# SUMO_ROBOT.net
KiCad netlist of a schematic drawn in EAGLE
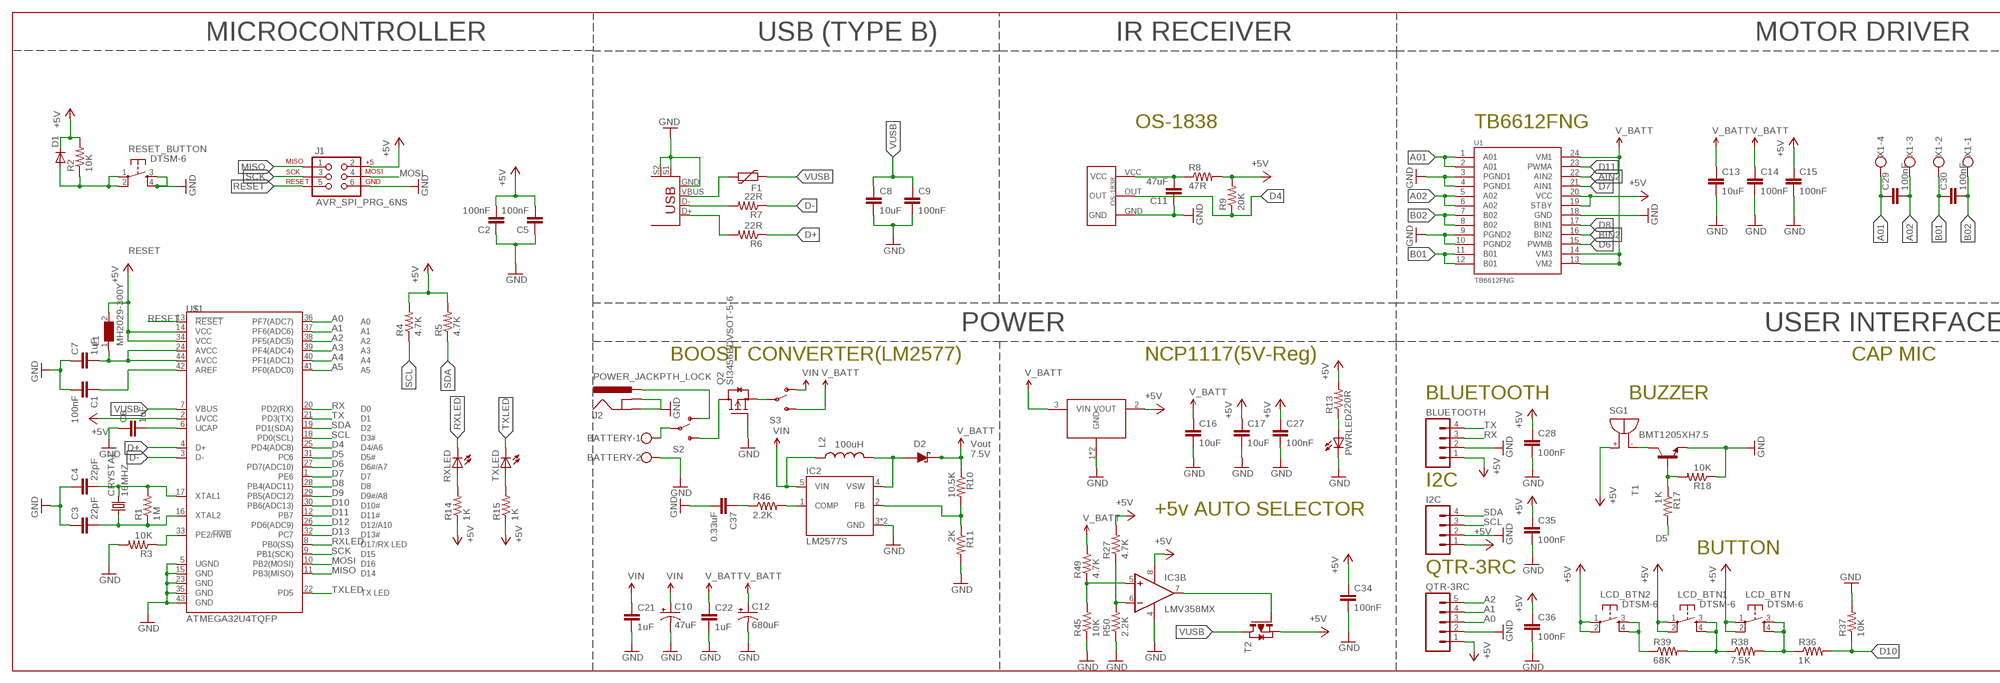
[diagram p0: schematic, sheet 1, part 1 of 2]
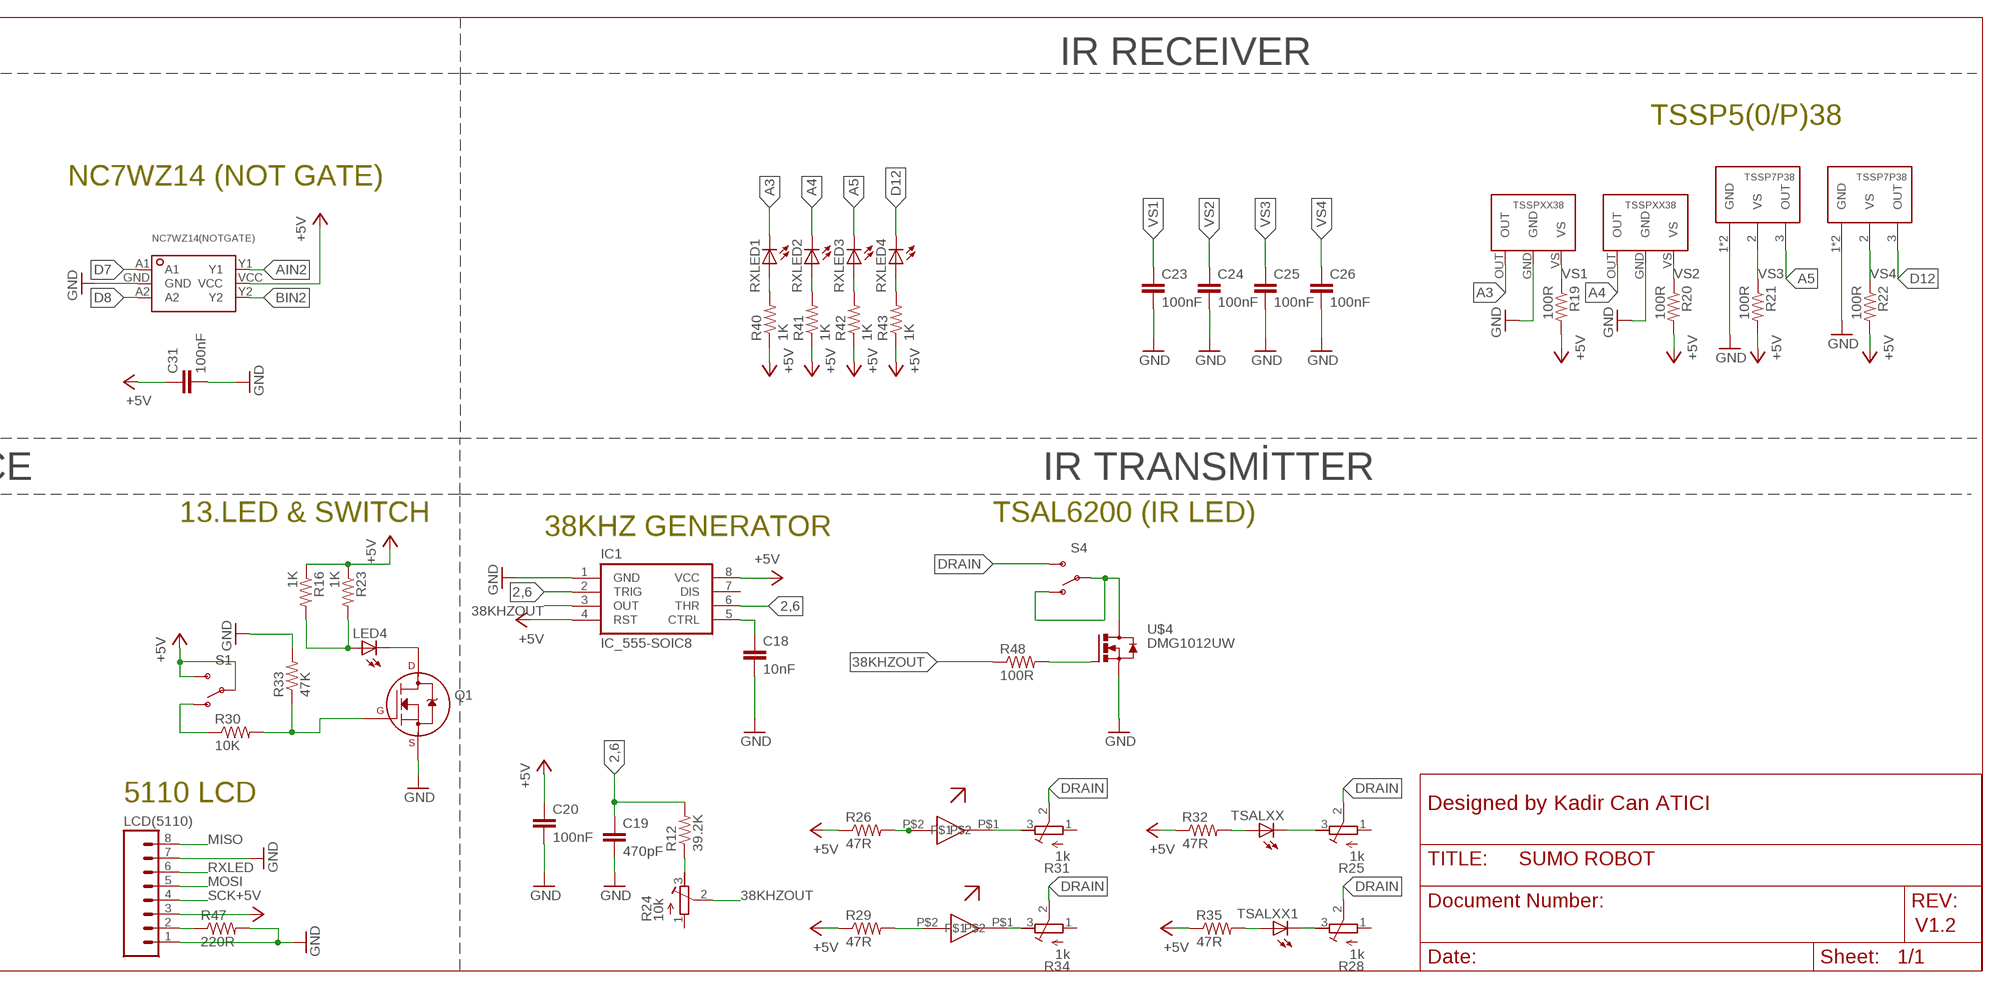
[diagram p1: schematic, sheet 1, part 2 of 2]

(export (version "E")
  (design (tool "Eeschema 10.0.6"))
  (components
    (comp (ref "BATTERY")
      (value "W237-102")
      (footprint "eagle-import:W237-102")
      (fields (field (name "MPN") "237-102"))
      (libsource (lib "eagle-import") (part "W237-102"))
    )
    (comp (ref "BLUETOOTH")
      (value "M04PTH")
      (footprint "eagle-import:1X04")
      (libsource (lib "eagle-import") (part "M04PTH"))
    )
    (comp (ref "C1")
      (value "100nF")
      (footprint "eagle-import:1206")
      (libsource (lib "eagle-import") (part "CAP1206"))
    )
    (comp (ref "C2")
      (value "100nF")
      (footprint "eagle-import:1206")
      (libsource (lib "eagle-import") (part "CAP1206"))
    )
    (comp (ref "C3")
      (value "22pF")
      (footprint "eagle-import:1206")
      (libsource (lib "eagle-import") (part "CAP1206"))
    )
    (comp (ref "C4")
      (value "22pF")
      (footprint "eagle-import:1206")
      (libsource (lib "eagle-import") (part "CAP1206"))
    )
    (comp (ref "C5")
      (value "100nF")
      (footprint "eagle-import:1206")
      (libsource (lib "eagle-import") (part "CAP1206"))
    )
    (comp (ref "C6")
      (value "1uF")
      (footprint "eagle-import:1206")
      (libsource (lib "eagle-import") (part "CAP1206"))
    )
    (comp (ref "C7")
      (value "1uF")
      (footprint "eagle-import:1206")
      (libsource (lib "eagle-import") (part "CAP1206"))
    )
    (comp (ref "C8")
      (value "10uF")
      (footprint "eagle-import:1206")
      (libsource (lib "eagle-import") (part "CAP1206"))
    )
    (comp (ref "C9")
      (value "100nF")
      (footprint "eagle-import:1206")
      (libsource (lib "eagle-import") (part "CAP1206"))
    )
    (comp (ref "C10")
      (value "47uF")
      (footprint "eagle-import:NIPPON_F80")
      (libsource (lib "eagle-import") (part "CAP_POLF80"))
    )
    (comp (ref "C11")
      (value "47uF")
      (footprint "eagle-import:1206")
      (libsource (lib "eagle-import") (part "CAP1206"))
    )
    (comp (ref "C12")
      (value "680uF")
      (footprint "eagle-import:PANASONIC_G")
      (libsource (lib "eagle-import") (part "CAP_POLG"))
    )
    (comp (ref "C13")
      (value "10uF")
      (footprint "eagle-import:1206")
      (libsource (lib "eagle-import") (part "CAP1206"))
    )
    (comp (ref "C14")
      (value "100nF")
      (footprint "eagle-import:1206")
      (libsource (lib "eagle-import") (part "CAP1206"))
    )
    (comp (ref "C15")
      (value "100nF")
      (footprint "eagle-import:1206")
      (libsource (lib "eagle-import") (part "CAP1206"))
    )
    (comp (ref "C16")
      (value "10uF")
      (footprint "eagle-import:1206")
      (libsource (lib "eagle-import") (part "CAP1206"))
    )
    (comp (ref "C17")
      (value "10uF")
      (footprint "eagle-import:1206")
      (libsource (lib "eagle-import") (part "CAP1206"))
    )
    (comp (ref "C18")
      (value "10nF")
      (footprint "eagle-import:1206")
      (libsource (lib "eagle-import") (part "CAP1206"))
    )
    (comp (ref "C19")
      (value "470pF")
      (footprint "eagle-import:1206")
      (libsource (lib "eagle-import") (part "CAP1206"))
    )
    (comp (ref "C20")
      (value "100nF")
      (footprint "eagle-import:1206")
      (libsource (lib "eagle-import") (part "CAP1206"))
    )
    (comp (ref "C21")
      (value "1uF")
      (footprint "eagle-import:1206")
      (libsource (lib "eagle-import") (part "CAP1206"))
    )
    (comp (ref "C22")
      (value "1uF")
      (footprint "eagle-import:1206")
      (libsource (lib "eagle-import") (part "CAP1206"))
    )
    (comp (ref "C23")
      (value "100nF")
      (footprint "eagle-import:1206")
      (libsource (lib "eagle-import") (part "CAP1206"))
    )
    (comp (ref "C24")
      (value "100nF")
      (footprint "eagle-import:1206")
      (libsource (lib "eagle-import") (part "CAP1206"))
    )
    (comp (ref "C25")
      (value "100nF")
      (footprint "eagle-import:1206")
      (libsource (lib "eagle-import") (part "CAP1206"))
    )
    (comp (ref "C26")
      (value "100nF")
      (footprint "eagle-import:1206")
      (libsource (lib "eagle-import") (part "CAP1206"))
    )
    (comp (ref "C27")
      (value "100nF")
      (footprint "eagle-import:1206")
      (libsource (lib "eagle-import") (part "CAP1206"))
    )
    (comp (ref "C28")
      (value "100nF")
      (footprint "eagle-import:1206")
      (libsource (lib "eagle-import") (part "CAP1206"))
    )
    (comp (ref "C29")
      (value "100nF")
      (footprint "eagle-import:1206")
      (libsource (lib "eagle-import") (part "CAP1206"))
    )
    (comp (ref "C30")
      (value "100nF")
      (footprint "eagle-import:1206")
      (libsource (lib "eagle-import") (part "CAP1206"))
    )
    (comp (ref "C31")
      (value "100nF")
      (footprint "eagle-import:1206")
      (libsource (lib "eagle-import") (part "CAP1206"))
    )
    (comp (ref "C34")
      (value "100nF")
      (footprint "eagle-import:1206")
      (libsource (lib "eagle-import") (part "CAP1206"))
    )
    (comp (ref "C35")
      (value "100nF")
      (footprint "eagle-import:1206")
      (libsource (lib "eagle-import") (part "CAP1206"))
    )
    (comp (ref "C36")
      (value "100nF")
      (footprint "eagle-import:1206")
      (libsource (lib "eagle-import") (part "CAP1206"))
    )
    (comp (ref "C37")
      (value "0.33uF")
      (footprint "eagle-import:1206")
      (libsource (lib "eagle-import") (part "CAP1206"))
    )
    (comp (ref "CRYSTAL")
      (value "16MHZ")
      (footprint "eagle-import:CRYSTAL-SMD-5X3")
      (libsource (lib "eagle-import") (part "CRYSTAL5X3"))
    )
    (comp (ref "D1")
      (value "DIODE-MINIMELF")
      (footprint "eagle-import:MINIMELF")
      (libsource (lib "eagle-import") (part "DIODE-MINIMELF"))
    )
    (comp (ref "D2")
      (value "D_SCHOTTKYA")
      (footprint "eagle-import:SMA")
      (libsource (lib "eagle-import") (part "D_SCHOTTKYA"))
    )
    (comp (ref "F1")
      (value "FUSE_PTC-0805")
      (footprint "eagle-import:PTC0805")
      (libsource (lib "eagle-import") (part "FUSE_PTC-0805"))
    )
    (comp (ref "I2C")
      (value "M04PTH")
      (footprint "eagle-import:1X04")
      (libsource (lib "eagle-import") (part "M04PTH"))
    )
    (comp (ref "IC1")
      (value "IC_555-SOIC8")
      (footprint "eagle-import:SOIC-8")
      (libsource (lib "eagle-import") (part "IC_555-SOIC8"))
    )
    (comp (ref "IC2")
      (value "LM2577S")
      (footprint "eagle-import:TO263-5")
      (libsource (lib "eagle-import") (part "LM2577S"))
    )
    (comp (ref "IC3")
      (value "LMV358MX")
      (footprint "eagle-import:SO08")
      (libsource (lib "eagle-import") (part "LMV358?MX"))
    )
    (comp (ref "J1")
      (value "AVR_SPI_PRG_6NS")
      (footprint "eagle-import:2X3-NS")
      (libsource (lib "eagle-import") (part "AVR_SPI_PRG_6NS"))
    )
    (comp (ref "J2")
      (value "POWER_JACKPTH_LOCK")
      (footprint "eagle-import:POWER_JACK_PTH_LOCK")
      (libsource (lib "eagle-import") (part "POWER_JACKPTH_LOCK"))
    )
    (comp (ref "L1")
      (value "MH2029-300Y")
      (footprint "eagle-import:0805")
      (libsource (lib "eagle-import") (part "WE-CBF_0805"))
    )
    (comp (ref "L2")
      (value "INDUCTORPWR")
      (footprint "eagle-import:CDRH125")
      (libsource (lib "eagle-import") (part "INDUCTORPWR"))
    )
    (comp (ref "LCD(5110)")
      (value "M081X08")
      (footprint "eagle-import:1X08")
      (libsource (lib "eagle-import") (part "M081X08"))
    )
    (comp (ref "LCD_BTN")
      (value "DTSM-6")
      (footprint "eagle-import:DTSM-6")
      (libsource (lib "eagle-import") (part "DTSM-6"))
    )
    (comp (ref "LCD_BTN1")
      (value "DTSM-6")
      (footprint "eagle-import:DTSM-6")
      (libsource (lib "eagle-import") (part "DTSM-6"))
    )
    (comp (ref "LCD_BTN2")
      (value "DTSM-6")
      (footprint "eagle-import:DTSM-6")
      (libsource (lib "eagle-import") (part "DTSM-6"))
    )
    (comp (ref "LED4")
      (value "LEDCHIPLED_0805")
      (footprint "eagle-import:CHIPLED_0805")
      (libsource (lib "eagle-import") (part "LEDCHIPLED_0805"))
    )
    (comp (ref "PWRLED")
      (value "LEDCHIPLED_0805")
      (footprint "eagle-import:CHIPLED_0805")
      (libsource (lib "eagle-import") (part "LEDCHIPLED_0805"))
    )
    (comp (ref "Q1")
      (value "2N7000_SOT23")
      (footprint "eagle-import:SOT-23")
      (libsource (lib "eagle-import") (part "2N700_SOT230"))
    )
    (comp (ref "Q2")
      (value "SI3456BDVSOT-5-6")
      (footprint "eagle-import:SOT23-6")
      (libsource (lib "eagle-import") (part "SI3456BDVSOT-5-6"))
    )
    (comp (ref "QTR-3RC")
      (value "M05PTH")
      (footprint "eagle-import:1X05")
      (libsource (lib "eagle-import") (part "M05PTH"))
    )
    (comp (ref "R1")
      (value "1M")
      (footprint "eagle-import:0805")
      (libsource (lib "eagle-import") (part "RESISTOR0805-RES"))
    )
    (comp (ref "R2")
      (value "10K")
      (footprint "eagle-import:0805")
      (libsource (lib "eagle-import") (part "RESISTOR0805-RES"))
    )
    (comp (ref "R3")
      (value "10K")
      (footprint "eagle-import:0805")
      (libsource (lib "eagle-import") (part "RESISTOR0805-RES"))
    )
    (comp (ref "R4")
      (value "4.7K")
      (footprint "eagle-import:0805")
      (libsource (lib "eagle-import") (part "RESISTOR0805-RES"))
    )
    (comp (ref "R5")
      (value "4.7K")
      (footprint "eagle-import:0805")
      (libsource (lib "eagle-import") (part "RESISTOR0805-RES"))
    )
    (comp (ref "R6")
      (value "22R")
      (footprint "eagle-import:0805")
      (libsource (lib "eagle-import") (part "RESISTOR0805-RES"))
    )
    (comp (ref "R7")
      (value "22R")
      (footprint "eagle-import:0805")
      (libsource (lib "eagle-import") (part "RESISTOR0805-RES"))
    )
    (comp (ref "R8")
      (value "47R")
      (footprint "eagle-import:0805")
      (libsource (lib "eagle-import") (part "RESISTOR0805-RES"))
    )
    (comp (ref "R9")
      (value "20K")
      (footprint "eagle-import:0805")
      (libsource (lib "eagle-import") (part "RESISTOR0805-RES"))
    )
    (comp (ref "R10")
      (value "10.5K")
      (footprint "eagle-import:0805")
      (libsource (lib "eagle-import") (part "RESISTOR0805-RES"))
    )
    (comp (ref "R11")
      (value "2K")
      (footprint "eagle-import:0805")
      (libsource (lib "eagle-import") (part "RESISTOR0805-RES"))
    )
    (comp (ref "R12")
      (value "39.2K")
      (footprint "eagle-import:0805")
      (libsource (lib "eagle-import") (part "RESISTOR0805-RES"))
    )
    (comp (ref "R13")
      (value "220R")
      (footprint "eagle-import:0805")
      (libsource (lib "eagle-import") (part "RESISTOR0805-RES"))
    )
    (comp (ref "R14")
      (value "1K")
      (footprint "eagle-import:0805")
      (libsource (lib "eagle-import") (part "RESISTOR0805-RES"))
    )
    (comp (ref "R15")
      (value "1K")
      (footprint "eagle-import:0805")
      (libsource (lib "eagle-import") (part "RESISTOR0805-RES"))
    )
    (comp (ref "R16")
      (value "1K")
      (footprint "eagle-import:0805")
      (libsource (lib "eagle-import") (part "RESISTOR0805-RES"))
    )
    (comp (ref "R17")
      (value "1K")
      (footprint "eagle-import:0805")
      (libsource (lib "eagle-import") (part "RESISTOR0805-RES"))
    )
    (comp (ref "R18")
      (value "10K")
      (footprint "eagle-import:0805")
      (libsource (lib "eagle-import") (part "RESISTOR0805-RES"))
    )
    (comp (ref "R19")
      (value "100R")
      (footprint "eagle-import:0805")
      (libsource (lib "eagle-import") (part "RESISTOR0805-RES"))
    )
    (comp (ref "R20")
      (value "100R")
      (footprint "eagle-import:0805")
      (libsource (lib "eagle-import") (part "RESISTOR0805-RES"))
    )
    (comp (ref "R21")
      (value "100R")
      (footprint "eagle-import:0805")
      (libsource (lib "eagle-import") (part "RESISTOR0805-RES"))
    )
    (comp (ref "R22")
      (value "100R")
      (footprint "eagle-import:0805")
      (libsource (lib "eagle-import") (part "RESISTOR0805-RES"))
    )
    (comp (ref "R23")
      (value "1K")
      (footprint "eagle-import:0805")
      (libsource (lib "eagle-import") (part "RESISTOR0805-RES"))
    )
    (comp (ref "R24")
      (value "10k")
      (footprint "eagle-import:RTRIM3296W")
      (libsource (lib "eagle-import") (part "R-TRIMM3296W"))
    )
    (comp (ref "R25")
      (value "1k")
      (footprint "eagle-import:RTRIM3296W")
      (libsource (lib "eagle-import") (part "R-TRIMM3296W"))
    )
    (comp (ref "R26")
      (value "47R")
      (footprint "eagle-import:0805")
      (libsource (lib "eagle-import") (part "RESISTOR0805-RES"))
    )
    (comp (ref "R27")
      (value "4.7K")
      (footprint "eagle-import:0805")
      (libsource (lib "eagle-import") (part "RESISTOR0805-RES"))
    )
    (comp (ref "R28")
      (value "1k")
      (footprint "eagle-import:RTRIM3296W")
      (libsource (lib "eagle-import") (part "R-TRIMM3296W"))
    )
    (comp (ref "R29")
      (value "47R")
      (footprint "eagle-import:0805")
      (libsource (lib "eagle-import") (part "RESISTOR0805-RES"))
    )
    (comp (ref "R30")
      (value "10K")
      (footprint "eagle-import:0805")
      (libsource (lib "eagle-import") (part "RESISTOR0805-RES"))
    )
    (comp (ref "R31")
      (value "1k")
      (footprint "eagle-import:RTRIM3296W")
      (libsource (lib "eagle-import") (part "R-TRIMM3296W"))
    )
    (comp (ref "R32")
      (value "47R")
      (footprint "eagle-import:0805")
      (libsource (lib "eagle-import") (part "RESISTOR0805-RES"))
    )
    (comp (ref "R33")
      (value "47K")
      (footprint "eagle-import:0805")
      (libsource (lib "eagle-import") (part "RESISTOR0805-RES"))
    )
    (comp (ref "R34")
      (value "1k")
      (footprint "eagle-import:RTRIM3296W")
      (libsource (lib "eagle-import") (part "R-TRIMM3296W"))
    )
    (comp (ref "R35")
      (value "47R")
      (footprint "eagle-import:0805")
      (libsource (lib "eagle-import") (part "RESISTOR0805-RES"))
    )
    (comp (ref "R36")
      (value "1K")
      (footprint "eagle-import:0805")
      (libsource (lib "eagle-import") (part "RESISTOR0805-RES"))
    )
    (comp (ref "R37")
      (value "10K")
      (footprint "eagle-import:0805")
      (libsource (lib "eagle-import") (part "RESISTOR0805-RES"))
    )
    (comp (ref "R38")
      (value "7.5K")
      (footprint "eagle-import:0805")
      (libsource (lib "eagle-import") (part "RESISTOR0805-RES"))
    )
    (comp (ref "R39")
      (value "68K")
      (footprint "eagle-import:0805")
      (libsource (lib "eagle-import") (part "RESISTOR0805-RES"))
    )
    (comp (ref "R40")
      (value "1K")
      (footprint "eagle-import:0805")
      (libsource (lib "eagle-import") (part "RESISTOR0805-RES"))
    )
    (comp (ref "R41")
      (value "1K")
      (footprint "eagle-import:0805")
      (libsource (lib "eagle-import") (part "RESISTOR0805-RES"))
    )
    (comp (ref "R42")
      (value "1K")
      (footprint "eagle-import:0805")
      (libsource (lib "eagle-import") (part "RESISTOR0805-RES"))
    )
    (comp (ref "R43")
      (value "1K")
      (footprint "eagle-import:0805")
      (libsource (lib "eagle-import") (part "RESISTOR0805-RES"))
    )
    (comp (ref "R45")
      (value "10K")
      (footprint "eagle-import:0805")
      (libsource (lib "eagle-import") (part "RESISTOR0805-RES"))
    )
    (comp (ref "R46")
      (value "2.2K")
      (footprint "eagle-import:0805")
      (libsource (lib "eagle-import") (part "RESISTOR0805-RES"))
    )
    (comp (ref "R47")
      (value "220R")
      (footprint "eagle-import:0805")
      (libsource (lib "eagle-import") (part "RESISTOR0805-RES"))
    )
    (comp (ref "R48")
      (value "100R")
      (footprint "eagle-import:0805")
      (libsource (lib "eagle-import") (part "RESISTOR0805-RES"))
    )
    (comp (ref "R49")
      (value "4.7K")
      (footprint "eagle-import:0805")
      (libsource (lib "eagle-import") (part "RESISTOR0805-RES"))
    )
    (comp (ref "R50")
      (value "2.2K")
      (footprint "eagle-import:0805")
      (libsource (lib "eagle-import") (part "RESISTOR0805-RES"))
    )
    (comp (ref "RESET_BUTTON")
      (value "DTSM-6")
      (footprint "eagle-import:DTSM-6")
      (libsource (lib "eagle-import") (part "DTSM-6"))
    )
    (comp (ref "RXLED")
      (value "LEDCHIPLED_0805")
      (footprint "eagle-import:CHIPLED_0805")
      (libsource (lib "eagle-import") (part "LEDCHIPLED_0805"))
    )
    (comp (ref "RXLED1")
      (value "LEDCHIPLED_0805")
      (footprint "eagle-import:CHIPLED_0805")
      (libsource (lib "eagle-import") (part "LEDCHIPLED_0805"))
    )
    (comp (ref "RXLED2")
      (value "LEDCHIPLED_0805")
      (footprint "eagle-import:CHIPLED_0805")
      (libsource (lib "eagle-import") (part "LEDCHIPLED_0805"))
    )
    (comp (ref "RXLED3")
      (value "LEDCHIPLED_0805")
      (footprint "eagle-import:CHIPLED_0805")
      (libsource (lib "eagle-import") (part "LEDCHIPLED_0805"))
    )
    (comp (ref "RXLED4")
      (value "LEDCHIPLED_0805")
      (footprint "eagle-import:CHIPLED_0805")
      (libsource (lib "eagle-import") (part "LEDCHIPLED_0805"))
    )
    (comp (ref "S1")
      (value "SWITCH-SPDTPTH")
      (footprint "eagle-import:SWITCH-SPDT")
      (libsource (lib "eagle-import") (part "SWITCH-SPDTPTH"))
    )
    (comp (ref "S2")
      (value "SWITCH-SPDTPTH")
      (footprint "eagle-import:SWITCH-SPDT")
      (libsource (lib "eagle-import") (part "SWITCH-SPDTPTH"))
    )
    (comp (ref "S3")
      (value "SWITCH-SPDTPTH")
      (footprint "eagle-import:SWITCH-SPDT")
      (libsource (lib "eagle-import") (part "SWITCH-SPDTPTH"))
    )
    (comp (ref "S4")
      (value "SWITCH-SPDTPTH")
      (footprint "eagle-import:SWITCH-SPDT")
      (libsource (lib "eagle-import") (part "SWITCH-SPDTPTH"))
    )
    (comp (ref "SG1")
      (value "BMT1205XH7.5")
      (footprint "eagle-import:BMT1205XH7.5")
      (libsource (lib "eagle-import") (part "BMT1205XH7.5"))
    )
    (comp (ref "T1")
      (value "MMBT2222ALT1-NPN-SOT23-BEC")
      (footprint "eagle-import:SOT23-BEC")
      (libsource (lib "eagle-import") (part "-NPN-SOT23-BECMMBT2222ALT1"))
    )
    (comp (ref "T2")
      (value "PMOSSOT23")
      (footprint "eagle-import:SOT-23")
      (libsource (lib "eagle-import") (part "PMOSSOT23"))
    )
    (comp (ref "TSALXX")
      (value "LED5MM")
      (footprint "eagle-import:LED5MM")
      (libsource (lib "eagle-import") (part "LED5MM"))
    )
    (comp (ref "TSALXX1")
      (value "LED5MM")
      (footprint "eagle-import:LED5MM")
      (libsource (lib "eagle-import") (part "LED5MM"))
    )
    (comp (ref "TXLED")
      (value "LEDCHIPLED_0805")
      (footprint "eagle-import:CHIPLED_0805")
      (libsource (lib "eagle-import") (part "LEDCHIPLED_0805"))
    )
    (comp (ref "U$1")
      (value "ATMEGA32U4TQFP")
      (footprint "eagle-import:SPARKFUN-DIGITALIC_TQFP44")
      (libsource (lib "eagle-import") (part "ATMEGA32U4TQFP"))
    )
    (comp (ref "U$2")
      (value "USB+SHIELD")
      (footprint "eagle-import:USB-B-PTH")
      (libsource (lib "eagle-import") (part "USB+SHIELD"))
    )
    (comp (ref "U$3")
      (value "OS-1838")
      (footprint "eagle-import:OS-1838")
      (libsource (lib "eagle-import") (part "OS-1838"))
    )
    (comp (ref "U$4")
      (value "DMG1012UW")
      (footprint "eagle-import:SOT323")
      (libsource (lib "eagle-import") (part "DMG1012UW"))
    )
    (comp (ref "U$5")
      (value "NCP1117")
      (footprint "eagle-import:SOT223")
      (libsource (lib "eagle-import") (part "NCP1117"))
    )
    (comp (ref "U$6")
      (value "TSSP7P38")
      (footprint "eagle-import:TSSP7P38")
      (libsource (lib "eagle-import") (part "TSSP7P38"))
    )
    (comp (ref "U$7")
      (value "TSSP7P38")
      (footprint "eagle-import:TSSP7P38")
      (libsource (lib "eagle-import") (part "TSSP7P38"))
    )
    (comp (ref "U$8")
      (value "TSSPXX38")
      (footprint "eagle-import:TSSPXX38")
      (libsource (lib "eagle-import") (part "TSSPXX38"))
    )
    (comp (ref "U$9")
      (value "TSSPXX38")
      (footprint "eagle-import:TSSPXX38")
      (libsource (lib "eagle-import") (part "TSSPXX38"))
    )
    (comp (ref "U$10")
      (value "NC7WZ14(NOTGATE)")
      (footprint "eagle-import:SC-70-6")
      (libsource (lib "eagle-import") (part "NC7WZ14(NOTGATE)"))
    )
    (comp (ref "U$11")
      (value "IRLED")
      (footprint "eagle-import:IRLED")
      (libsource (lib "eagle-import") (part "IRLED"))
    )
    (comp (ref "U$12")
      (value "IRLED")
      (footprint "eagle-import:IRLED")
      (libsource (lib "eagle-import") (part "IRLED"))
    )
    (comp (ref "U1")
      (value "TB6612FNG")
      (footprint "eagle-import:SSOP24")
      (libsource (lib "eagle-import") (part "TB6621FNG"))
    )
    (comp (ref "X1")
      (value "W237-4")
      (footprint "eagle-import:W237-4")
      (libsource (lib "eagle-import") (part "W237-4"))
    )
  )
  (nets
    (net (code "1") (name "+5V") (class "Default")
      (node (ref "BLUETOOTH") (pin "1") (pinfunction "1_1") (pintype "passive"))
      (node (ref "C15") (pin "1") (pinfunction "1_1") (pintype "passive"))
      (node (ref "C17") (pin "1") (pinfunction "1_1") (pintype "passive"))
      (node (ref "C2") (pin "2") (pinfunction "2_2") (pintype "passive"))
      (node (ref "C20") (pin "1") (pinfunction "1_1") (pintype "passive"))
      (node (ref "C27") (pin "1") (pinfunction "1_1") (pintype "passive"))
      (node (ref "C28") (pin "1") (pinfunction "1_1") (pintype "passive"))
      (node (ref "C31") (pin "1") (pinfunction "1_1") (pintype "passive"))
      (node (ref "C34") (pin "1") (pinfunction "1_1") (pintype "passive"))
      (node (ref "C35") (pin "1") (pinfunction "1_1") (pintype "passive"))
      (node (ref "C36") (pin "1") (pinfunction "1_1") (pintype "passive"))
      (node (ref "C5") (pin "2") (pinfunction "2_2") (pintype "passive"))
      (node (ref "D1") (pin "C") (pinfunction "C_C") (pintype "passive"))
      (node (ref "I2C") (pin "1") (pinfunction "1_1") (pintype "passive"))
      (node (ref "IC1") (pin "4") (pinfunction "RST_4") (pintype "input"))
      (node (ref "IC1") (pin "8") (pinfunction "VCC_8") (pintype "power_in"))
      (node (ref "IC3") (pin "8") (pinfunction "V+_8") (pintype "power_in"))
      (node (ref "J1") (pin "2") (pinfunction "2_2") (pintype "passive"))
      (node (ref "L1") (pin "2") (pinfunction "2_2") (pintype "passive"))
      (node (ref "LCD(5110)") (pin "3") (pinfunction "3_3") (pintype "passive"))
      (node (ref "LCD_BTN") (pin "1") (pinfunction "1_1") (pintype "passive"))
      (node (ref "LCD_BTN") (pin "2") (pinfunction "2_2") (pintype "passive"))
      (node (ref "LCD_BTN1") (pin "1") (pinfunction "1_1") (pintype "passive"))
      (node (ref "LCD_BTN1") (pin "2") (pinfunction "2_2") (pintype "passive"))
      (node (ref "LCD_BTN2") (pin "1") (pinfunction "1_1") (pintype "passive"))
      (node (ref "LCD_BTN2") (pin "2") (pinfunction "2_2") (pintype "passive"))
      (node (ref "QTR-3RC") (pin "1") (pinfunction "1_1") (pintype "passive"))
      (node (ref "R13") (pin "2") (pinfunction "2_2") (pintype "passive"))
      (node (ref "R14") (pin "1") (pinfunction "1_1") (pintype "passive"))
      (node (ref "R15") (pin "1") (pinfunction "1_1") (pintype "passive"))
      (node (ref "R16") (pin "1") (pinfunction "1_1") (pintype "passive"))
      (node (ref "R19") (pin "2") (pinfunction "2_2") (pintype "passive"))
      (node (ref "R2") (pin "2") (pinfunction "2_2") (pintype "passive"))
      (node (ref "R20") (pin "2") (pinfunction "2_2") (pintype "passive"))
      (node (ref "R21") (pin "2") (pinfunction "2_2") (pintype "passive"))
      (node (ref "R22") (pin "2") (pinfunction "2_2") (pintype "passive"))
      (node (ref "R23") (pin "1") (pinfunction "1_1") (pintype "passive"))
      (node (ref "R26") (pin "1") (pinfunction "1_1") (pintype "passive"))
      (node (ref "R27") (pin "2") (pinfunction "2_2") (pintype "passive"))
      (node (ref "R29") (pin "1") (pinfunction "1_1") (pintype "passive"))
      (node (ref "R32") (pin "1") (pinfunction "1_1") (pintype "passive"))
      (node (ref "R35") (pin "1") (pinfunction "1_1") (pintype "passive"))
      (node (ref "R4") (pin "2") (pinfunction "2_2") (pintype "passive"))
      (node (ref "R40") (pin "1") (pinfunction "1_1") (pintype "passive"))
      (node (ref "R41") (pin "1") (pinfunction "1_1") (pintype "passive"))
      (node (ref "R42") (pin "1") (pinfunction "1_1") (pintype "passive"))
      (node (ref "R43") (pin "1") (pinfunction "1_1") (pintype "passive"))
      (node (ref "R5") (pin "2") (pinfunction "2_2") (pintype "passive"))
      (node (ref "R8") (pin "2") (pinfunction "2_2") (pintype "passive"))
      (node (ref "R9") (pin "2") (pinfunction "2_2") (pintype "passive"))
      (node (ref "S1") (pin "2") (pinfunction "P_2") (pintype "passive"))
      (node (ref "S1") (pin "3") (pinfunction "S_3") (pintype "passive"))
      (node (ref "SG1") (pin "+") (pinfunction "+_+") (pintype "passive"))
      (node (ref "T2") (pin "2") (pinfunction "S_2") (pintype "passive"))
      (node (ref "U$1") (pin "14") (pinfunction "VCC_14") (pintype "bidirectional"))
      (node (ref "U$1") (pin "2") (pinfunction "UVCC_2") (pintype "bidirectional"))
      (node (ref "U$1") (pin "34") (pinfunction "VCC_34") (pintype "bidirectional"))
      (node (ref "U$10") (pin "VCC") (pinfunction "VCC_VCC") (pintype "bidirectional"))
      (node (ref "U$5") (pin "2") (pinfunction "VOUT_2") (pintype "bidirectional"))
      (node (ref "U1") (pin "19") (pinfunction "STBY_19") (pintype "bidirectional"))
      (node (ref "U1") (pin "20") (pinfunction "VCC_20") (pintype "bidirectional"))
    )
    (net (code "2") (name "/A0") (class "Default")
      (node (ref "QTR-3RC") (pin "3") (pinfunction "3_3") (pintype "passive"))
      (node (ref "U$1") (pin "36") (pinfunction "PF7(ADC7)_36") (pintype "bidirectional"))
    )
    (net (code "3") (name "/A1") (class "Default")
      (node (ref "QTR-3RC") (pin "4") (pinfunction "4_4") (pintype "passive"))
      (node (ref "U$1") (pin "37") (pinfunction "PF6(ADC6)_37") (pintype "bidirectional"))
    )
    (net (code "4") (name "/A2") (class "Default")
      (node (ref "QTR-3RC") (pin "5") (pinfunction "5_5") (pintype "passive"))
      (node (ref "U$1") (pin "38") (pinfunction "PF5(ADC5)_38") (pintype "bidirectional"))
    )
    (net (code "5") (name "/D5") (class "Default")
      (node (ref "R17") (pin "2") (pinfunction "2_2") (pintype "passive"))
      (node (ref "U$1") (pin "31") (pinfunction "PC6_31") (pintype "bidirectional"))
    )
    (net (code "6") (name "/D9") (class "Default")
      (node (ref "U$1") (pin "29") (pinfunction "PB5(ADC12)_29") (pintype "bidirectional"))
    )
    (net (code "7") (name "/D13") (class "Default")
      (node (ref "U$1") (pin "32") (pinfunction "PC7_32") (pintype "bidirectional"))
    )
    (net (code "8") (name "/MOSI") (class "Default")
      (node (ref "J1") (pin "4") (pinfunction "4_4") (pintype "passive"))
      (node (ref "LCD(5110)") (pin "5") (pinfunction "5_5") (pintype "passive"))
      (node (ref "U$1") (pin "10") (pinfunction "PB2(MOSI)_10") (pintype "bidirectional"))
    )
    (net (code "9") (name "/RX") (class "Default")
      (node (ref "BLUETOOTH") (pin "3") (pinfunction "3_3") (pintype "passive"))
      (node (ref "U$1") (pin "20") (pinfunction "PD2(RX)_20") (pintype "bidirectional"))
    )
    (net (code "10") (name "/TX") (class "Default")
      (node (ref "BLUETOOTH") (pin "4") (pinfunction "4_4") (pintype "passive"))
      (node (ref "U$1") (pin "21") (pinfunction "PD3(TX)_21") (pintype "bidirectional"))
    )
    (net (code "11") (name "2,6") (class "Default")
      (node (ref "C19") (pin "1") (pinfunction "1_1") (pintype "passive"))
      (node (ref "IC1") (pin "2") (pinfunction "TRIG_2") (pintype "input"))
      (node (ref "IC1") (pin "6") (pinfunction "THR_6") (pintype "input"))
      (node (ref "R12") (pin "2") (pinfunction "2_2") (pintype "passive"))
    )
    (net (code "12") (name "38KHZOUT") (class "Default")
      (node (ref "IC1") (pin "3") (pinfunction "OUT_3") (pintype "output"))
      (node (ref "R24") (pin "2") (pinfunction "S_2") (pintype "passive"))
      (node (ref "R48") (pin "1") (pinfunction "1_1") (pintype "passive"))
    )
    (net (code "13") (name "A01") (class "Default")
      (node (ref "C29") (pin "1") (pinfunction "1_1") (pintype "passive"))
      (node (ref "U1") (pin "1") (pinfunction "A01_1") (pintype "bidirectional"))
      (node (ref "U1") (pin "2") (pinfunction "A01_2") (pintype "bidirectional"))
      (node (ref "X1") (pin "4") (pinfunction "KL_4") (pintype "passive"))
    )
    (net (code "14") (name "A02") (class "Default")
      (node (ref "C29") (pin "2") (pinfunction "2_2") (pintype "passive"))
      (node (ref "U1") (pin "5") (pinfunction "A02_5") (pintype "bidirectional"))
      (node (ref "U1") (pin "6") (pinfunction "A02_6") (pintype "bidirectional"))
      (node (ref "X1") (pin "3") (pinfunction "KL_3") (pintype "passive"))
    )
    (net (code "15") (name "A3") (class "Default")
      (node (ref "RXLED1") (pin "C") (pinfunction "C_C") (pintype "passive"))
      (node (ref "U$1") (pin "39") (pinfunction "PF4(ADC4)_39") (pintype "bidirectional"))
      (node (ref "U$9") (pin "OUT") (pinfunction "OUT_OUT") (pintype "bidirectional"))
    )
    (net (code "16") (name "A4") (class "Default")
      (node (ref "RXLED2") (pin "C") (pinfunction "C_C") (pintype "passive"))
      (node (ref "U$1") (pin "40") (pinfunction "PF1(ADC1)_40") (pintype "bidirectional"))
      (node (ref "U$8") (pin "OUT") (pinfunction "OUT_OUT") (pintype "bidirectional"))
    )
    (net (code "17") (name "A5") (class "Default")
      (node (ref "RXLED3") (pin "C") (pinfunction "C_C") (pintype "passive"))
      (node (ref "U$1") (pin "41") (pinfunction "PF0(ADC0)_41") (pintype "bidirectional"))
      (node (ref "U$6") (pin "3") (pinfunction "OUT_3") (pintype "bidirectional"))
    )
    (net (code "18") (name "AIN2") (class "Default")
      (node (ref "U$10") (pin "Y1") (pinfunction "Y1_Y1") (pintype "bidirectional"))
      (node (ref "U1") (pin "22") (pinfunction "AIN2_22") (pintype "bidirectional"))
    )
    (net (code "19") (name "B01") (class "Default")
      (node (ref "C30") (pin "1") (pinfunction "1_1") (pintype "passive"))
      (node (ref "U1") (pin "11") (pinfunction "B01_11") (pintype "bidirectional"))
      (node (ref "U1") (pin "12") (pinfunction "B01_12") (pintype "bidirectional"))
      (node (ref "X1") (pin "2") (pinfunction "KL_2") (pintype "passive"))
    )
    (net (code "20") (name "B02") (class "Default")
      (node (ref "C30") (pin "2") (pinfunction "2_2") (pintype "passive"))
      (node (ref "U1") (pin "7") (pinfunction "B02_7") (pintype "bidirectional"))
      (node (ref "U1") (pin "8") (pinfunction "B02_8") (pintype "bidirectional"))
      (node (ref "X1") (pin "1") (pinfunction "KL_1") (pintype "passive"))
    )
    (net (code "21") (name "BIN2") (class "Default")
      (node (ref "U$10") (pin "Y2") (pinfunction "Y2_Y2") (pintype "bidirectional"))
      (node (ref "U1") (pin "16") (pinfunction "BIN2_16") (pintype "bidirectional"))
    )
    (net (code "22") (name "D+") (class "Default")
      (node (ref "R6") (pin "1") (pinfunction "1_1") (pintype "passive"))
      (node (ref "U$1") (pin "4") (pinfunction "D+_4") (pintype "bidirectional"))
    )
    (net (code "23") (name "D-") (class "Default")
      (node (ref "R7") (pin "1") (pinfunction "1_1") (pintype "passive"))
      (node (ref "U$1") (pin "3") (pinfunction "D-_3") (pintype "bidirectional"))
    )
    (net (code "24") (name "D4") (class "Default")
      (node (ref "R9") (pin "1") (pinfunction "1_1") (pintype "passive"))
      (node (ref "U$1") (pin "25") (pinfunction "PD4(ADC8)_25") (pintype "bidirectional"))
      (node (ref "U$3") (pin "OUT") (pinfunction "OUT_OUT") (pintype "bidirectional"))
    )
    (net (code "25") (name "D6") (class "Default")
      (node (ref "U$1") (pin "27") (pinfunction "PD7(ADC10)_27") (pintype "bidirectional"))
      (node (ref "U1") (pin "15") (pinfunction "PWMB_15") (pintype "bidirectional"))
    )
    (net (code "26") (name "D7") (class "Default")
      (node (ref "U$1") (pin "1") (pinfunction "PE6_1") (pintype "bidirectional"))
      (node (ref "U$10") (pin "A1") (pinfunction "A1_A1") (pintype "bidirectional"))
      (node (ref "U1") (pin "21") (pinfunction "AIN1_21") (pintype "bidirectional"))
    )
    (net (code "27") (name "D8") (class "Default")
      (node (ref "U$1") (pin "28") (pinfunction "PB4(ADC11)_28") (pintype "bidirectional"))
      (node (ref "U$10") (pin "A2") (pinfunction "A2_A2") (pintype "bidirectional"))
      (node (ref "U1") (pin "17") (pinfunction "BIN1_17") (pintype "bidirectional"))
    )
    (net (code "28") (name "D10") (class "Default")
      (node (ref "R36") (pin "2") (pinfunction "2_2") (pintype "passive"))
      (node (ref "R37") (pin "1") (pinfunction "1_1") (pintype "passive"))
      (node (ref "U$1") (pin "30") (pinfunction "PB6(ADC13)_30") (pintype "bidirectional"))
    )
    (net (code "29") (name "D11") (class "Default")
      (node (ref "U$1") (pin "12") (pinfunction "PB7_12") (pintype "bidirectional"))
      (node (ref "U1") (pin "23") (pinfunction "PWMA_23") (pintype "bidirectional"))
    )
    (net (code "30") (name "D12") (class "Default")
      (node (ref "RXLED4") (pin "C") (pinfunction "C_C") (pintype "passive"))
      (node (ref "U$1") (pin "26") (pinfunction "PD6(ADC9)_26") (pintype "bidirectional"))
      (node (ref "U$7") (pin "3") (pinfunction "OUT_3") (pintype "bidirectional"))
    )
    (net (code "31") (name "DRAIN") (class "Default")
      (node (ref "R25") (pin "2") (pinfunction "S_2") (pintype "passive"))
      (node (ref "R28") (pin "2") (pinfunction "S_2") (pintype "passive"))
      (node (ref "R31") (pin "2") (pinfunction "S_2") (pintype "passive"))
      (node (ref "R34") (pin "2") (pinfunction "S_2") (pintype "passive"))
      (node (ref "S4") (pin "3") (pinfunction "S_3") (pintype "passive"))
    )
    (net (code "32") (name "GND") (class "Default")
      (node (ref "BATTERY") (pin "2") (pinfunction "KL_2") (pintype "passive"))
      (node (ref "BLUETOOTH") (pin "2") (pinfunction "2_2") (pintype "passive"))
      (node (ref "C1") (pin "2") (pinfunction "2_2") (pintype "passive"))
      (node (ref "C10") (pin "-") (pinfunction "-_-") (pintype "passive"))
      (node (ref "C11") (pin "1") (pinfunction "1_1") (pintype "passive"))
      (node (ref "C12") (pin "-") (pinfunction "-_-") (pintype "passive"))
      (node (ref "C13") (pin "2") (pinfunction "2_2") (pintype "passive"))
      (node (ref "C14") (pin "2") (pinfunction "2_2") (pintype "passive"))
      (node (ref "C15") (pin "2") (pinfunction "2_2") (pintype "passive"))
      (node (ref "C16") (pin "2") (pinfunction "2_2") (pintype "passive"))
      (node (ref "C17") (pin "2") (pinfunction "2_2") (pintype "passive"))
      (node (ref "C18") (pin "2") (pinfunction "2_2") (pintype "passive"))
      (node (ref "C19") (pin "2") (pinfunction "2_2") (pintype "passive"))
      (node (ref "C2") (pin "1") (pinfunction "1_1") (pintype "passive"))
      (node (ref "C20") (pin "2") (pinfunction "2_2") (pintype "passive"))
      (node (ref "C21") (pin "2") (pinfunction "2_2") (pintype "passive"))
      (node (ref "C22") (pin "2") (pinfunction "2_2") (pintype "passive"))
      (node (ref "C23") (pin "2") (pinfunction "2_2") (pintype "passive"))
      (node (ref "C24") (pin "2") (pinfunction "2_2") (pintype "passive"))
      (node (ref "C25") (pin "2") (pinfunction "2_2") (pintype "passive"))
      (node (ref "C26") (pin "2") (pinfunction "2_2") (pintype "passive"))
      (node (ref "C27") (pin "2") (pinfunction "2_2") (pintype "passive"))
      (node (ref "C28") (pin "2") (pinfunction "2_2") (pintype "passive"))
      (node (ref "C3") (pin "1") (pinfunction "1_1") (pintype "passive"))
      (node (ref "C31") (pin "2") (pinfunction "2_2") (pintype "passive"))
      (node (ref "C34") (pin "2") (pinfunction "2_2") (pintype "passive"))
      (node (ref "C35") (pin "2") (pinfunction "2_2") (pintype "passive"))
      (node (ref "C36") (pin "2") (pinfunction "2_2") (pintype "passive"))
      (node (ref "C37") (pin "2") (pinfunction "2_2") (pintype "passive"))
      (node (ref "C4") (pin "1") (pinfunction "1_1") (pintype "passive"))
      (node (ref "C5") (pin "1") (pinfunction "1_1") (pintype "passive"))
      (node (ref "C6") (pin "1") (pinfunction "1_1") (pintype "passive"))
      (node (ref "C7") (pin "1") (pinfunction "1_1") (pintype "passive"))
      (node (ref "C8") (pin "2") (pinfunction "2_2") (pintype "passive"))
      (node (ref "C9") (pin "2") (pinfunction "2_2") (pintype "passive"))
      (node (ref "I2C") (pin "2") (pinfunction "2_2") (pintype "passive"))
      (node (ref "IC1") (pin "1") (pinfunction "GND_1") (pintype "power_in"))
      (node (ref "IC2") (pin "3") (pinfunction "GND_3") (pintype "power_in"))
      (node (ref "IC2") (pin "6") (pinfunction "GND_6") (pintype "power_in"))
      (node (ref "IC3") (pin "4") (pinfunction "V-_4") (pintype "power_in"))
      (node (ref "J1") (pin "6") (pinfunction "6_6") (pintype "passive"))
      (node (ref "J2") (pin "GND") (pinfunction "GND_GND") (pintype "bidirectional"))
      (node (ref "J2") (pin "GNDBREAK") (pinfunction "GNDBREAK_GNDBREAK") (pintype "bidirectional"))
      (node (ref "LCD(5110)") (pin "1") (pinfunction "1_1") (pintype "passive"))
      (node (ref "LCD(5110)") (pin "7") (pinfunction "7_7") (pintype "passive"))
      (node (ref "PWRLED") (pin "C") (pinfunction "C_C") (pintype "passive"))
      (node (ref "Q1") (pin "2") (pinfunction "S_2") (pintype "bidirectional"))
      (node (ref "Q2") (pin "3") (pinfunction "G_3") (pintype "passive"))
      (node (ref "QTR-3RC") (pin "2") (pinfunction "2_2") (pintype "passive"))
      (node (ref "R11") (pin "2") (pinfunction "2_2") (pintype "passive"))
      (node (ref "R18") (pin "1") (pinfunction "1_1") (pintype "passive"))
      (node (ref "R3") (pin "2") (pinfunction "2_2") (pintype "passive"))
      (node (ref "R33") (pin "2") (pinfunction "2_2") (pintype "passive"))
      (node (ref "R37") (pin "2") (pinfunction "2_2") (pintype "passive"))
      (node (ref "R45") (pin "1") (pinfunction "1_1") (pintype "passive"))
      (node (ref "R47") (pin "2") (pinfunction "2_2") (pintype "passive"))
      (node (ref "R50") (pin "1") (pinfunction "1_1") (pintype "passive"))
      (node (ref "RESET_BUTTON") (pin "3") (pinfunction "3_3") (pintype "passive"))
      (node (ref "RESET_BUTTON") (pin "4") (pinfunction "4_4") (pintype "passive"))
      (node (ref "T1") (pin "E") (pinfunction "E_E") (pintype "passive"))
      (node (ref "U$1") (pin "15") (pinfunction "GND_15") (pintype "bidirectional"))
      (node (ref "U$1") (pin "23") (pinfunction "GND_23") (pintype "bidirectional"))
      (node (ref "U$1") (pin "35") (pinfunction "GND_35") (pintype "bidirectional"))
      (node (ref "U$1") (pin "43") (pinfunction "GND_43") (pintype "bidirectional"))
      (node (ref "U$1") (pin "5") (pinfunction "UGND_5") (pintype "bidirectional"))
      (node (ref "U$10") (pin "GND") (pinfunction "GND_GND") (pintype "bidirectional"))
      (node (ref "U$2") (pin "GND") (pinfunction "GND_GND") (pintype "bidirectional"))
      (node (ref "U$2") (pin "S1") (pinfunction "S1_S1") (pintype "bidirectional"))
      (node (ref "U$2") (pin "S2") (pinfunction "S2_S2") (pintype "bidirectional"))
      (node (ref "U$3") (pin "GND") (pinfunction "GND_GND") (pintype "bidirectional"))
      (node (ref "U$4") (pin "2") (pinfunction "S_2") (pintype "passive"))
      (node (ref "U$5") (pin "1") (pinfunction "GND_1") (pintype "bidirectional"))
      (node (ref "U$5") (pin "4") (pinfunction "GND_4") (pintype "bidirectional"))
      (node (ref "U$6") (pin "1") (pinfunction "GND_1") (pintype "bidirectional"))
      (node (ref "U$6") (pin "4") (pinfunction "GND_4") (pintype "bidirectional"))
      (node (ref "U$7") (pin "1") (pinfunction "GND_1") (pintype "bidirectional"))
      (node (ref "U$7") (pin "4") (pinfunction "GND_4") (pintype "bidirectional"))
      (node (ref "U$8") (pin "GND") (pinfunction "GND_GND") (pintype "bidirectional"))
      (node (ref "U$9") (pin "GND") (pinfunction "GND_GND") (pintype "bidirectional"))
      (node (ref "U1") (pin "10") (pinfunction "PGND2_10") (pintype "bidirectional"))
      (node (ref "U1") (pin "18") (pinfunction "GND_18") (pintype "bidirectional"))
      (node (ref "U1") (pin "3") (pinfunction "PGND1_3") (pintype "bidirectional"))
      (node (ref "U1") (pin "4") (pinfunction "PGND1_4") (pintype "bidirectional"))
      (node (ref "U1") (pin "9") (pinfunction "PGND2_9") (pintype "bidirectional"))
    )
    (net (code "33") (name "MISO") (class "Default")
      (node (ref "J1") (pin "1") (pinfunction "1_1") (pintype "passive"))
      (node (ref "LCD(5110)") (pin "8") (pinfunction "8_8") (pintype "passive"))
      (node (ref "U$1") (pin "11") (pinfunction "PB3(MISO)_11") (pintype "bidirectional"))
    )
    (net (code "34") (name "Net-(BATTERYA-KL)") (class "Default")
      (node (ref "BATTERY") (pin "1") (pinfunction "KL_1") (pintype "passive"))
      (node (ref "S2") (pin "2") (pinfunction "P_2") (pintype "passive"))
    )
    (net (code "35") (name "Net-(C7-Pad2)") (class "Default")
      (node (ref "C7") (pin "2") (pinfunction "2_2") (pintype "passive"))
      (node (ref "L1") (pin "1") (pinfunction "1_1") (pintype "passive"))
      (node (ref "U$1") (pin "24") (pinfunction "AVCC_24") (pintype "bidirectional"))
      (node (ref "U$1") (pin "44") (pinfunction "AVCC_44") (pintype "bidirectional"))
    )
    (net (code "36") (name "Net-(C11-Pad2)") (class "Default")
      (node (ref "C11") (pin "2") (pinfunction "2_2") (pintype "passive"))
      (node (ref "R8") (pin "1") (pinfunction "1_1") (pintype "passive"))
      (node (ref "U$3") (pin "VCC") (pinfunction "VCC_VCC") (pintype "bidirectional"))
    )
    (net (code "37") (name "Net-(C37-Pad1)") (class "Default")
      (node (ref "C37") (pin "1") (pinfunction "1_1") (pintype "passive"))
      (node (ref "R46") (pin "1") (pinfunction "1_1") (pintype "passive"))
    )
    (net (code "38") (name "Net-(CRYSTAL-2)") (class "Default")
      (node (ref "C4") (pin "2") (pinfunction "2_2") (pintype "passive"))
      (node (ref "CRYSTAL") (pin "3") (pinfunction "2_3") (pintype "passive"))
      (node (ref "R1") (pin "2") (pinfunction "2_2") (pintype "passive"))
      (node (ref "U$1") (pin "17") (pinfunction "XTAL1_17") (pintype "bidirectional"))
    )
    (net (code "39") (name "Net-(D2-A)") (class "Default")
      (node (ref "D2") (pin "2") (pinfunction "A_2") (pintype "passive"))
      (node (ref "IC2") (pin "4") (pinfunction "VSW_4") (pintype "bidirectional"))
      (node (ref "L2") (pin "2") (pinfunction "2_2") (pintype "passive"))
    )
    (net (code "40") (name "Net-(F1-Pad2)") (class "Default")
      (node (ref "F1") (pin "2") (pinfunction "2_2") (pintype "passive"))
      (node (ref "U$2") (pin "VBUS") (pinfunction "VBUS_VBUS") (pintype "bidirectional"))
    )
    (net (code "41") (name "Net-(IC1-CTRL)") (class "Default")
      (node (ref "C18") (pin "1") (pinfunction "1_1") (pintype "passive"))
      (node (ref "IC1") (pin "5") (pinfunction "CTRL_5") (pintype "power_in"))
    )
    (net (code "42") (name "Net-(IC2-COMP)") (class "Default")
      (node (ref "IC2") (pin "1") (pinfunction "COMP_1") (pintype "passive"))
      (node (ref "R46") (pin "2") (pinfunction "2_2") (pintype "passive"))
    )
    (net (code "43") (name "Net-(IC2-FB)") (class "Default")
      (node (ref "IC2") (pin "2") (pinfunction "FB_2") (pintype "input"))
      (node (ref "R10") (pin "2") (pinfunction "2_2") (pintype "passive"))
      (node (ref "R11") (pin "1") (pinfunction "1_1") (pintype "passive"))
    )
    (net (code "44") (name "Net-(IC3B-+IN)") (class "Default")
      (node (ref "IC3") (pin "5") (pinfunction "+IN_5") (pintype "input"))
      (node (ref "R45") (pin "2") (pinfunction "2_2") (pintype "passive"))
      (node (ref "R49") (pin "1") (pinfunction "1_1") (pintype "passive"))
    )
    (net (code "45") (name "Net-(IC3B--IN)") (class "Default")
      (node (ref "IC3") (pin "6") (pinfunction "-IN_6") (pintype "input"))
      (node (ref "R27") (pin "1") (pinfunction "1_1") (pintype "passive"))
      (node (ref "R50") (pin "2") (pinfunction "2_2") (pintype "passive"))
    )
    (net (code "46") (name "Net-(IC3B-OUT)") (class "Default")
      (node (ref "IC3") (pin "7") (pinfunction "OUT_7") (pintype "output"))
      (node (ref "T2") (pin "3") (pinfunction "G_3") (pintype "passive"))
    )
    (net (code "47") (name "Net-(LCD(5110)-Pad2)") (class "Default")
      (node (ref "LCD(5110)") (pin "2") (pinfunction "2_2") (pintype "passive"))
      (node (ref "R47") (pin "1") (pinfunction "1_1") (pintype "passive"))
    )
    (net (code "48") (name "Net-(LCD_BTN-Pad3)") (class "Default")
      (node (ref "LCD_BTN") (pin "3") (pinfunction "3_3") (pintype "passive"))
      (node (ref "LCD_BTN") (pin "4") (pinfunction "4_4") (pintype "passive"))
      (node (ref "R36") (pin "1") (pinfunction "1_1") (pintype "passive"))
      (node (ref "R38") (pin "2") (pinfunction "2_2") (pintype "passive"))
    )
    (net (code "49") (name "Net-(LCD_BTN1-Pad3)") (class "Default")
      (node (ref "LCD_BTN1") (pin "3") (pinfunction "3_3") (pintype "passive"))
      (node (ref "LCD_BTN1") (pin "4") (pinfunction "4_4") (pintype "passive"))
      (node (ref "R38") (pin "1") (pinfunction "1_1") (pintype "passive"))
      (node (ref "R39") (pin "2") (pinfunction "2_2") (pintype "passive"))
    )
    (net (code "50") (name "Net-(LCD_BTN2-Pad3)") (class "Default")
      (node (ref "LCD_BTN2") (pin "3") (pinfunction "3_3") (pintype "passive"))
      (node (ref "LCD_BTN2") (pin "4") (pinfunction "4_4") (pintype "passive"))
      (node (ref "R39") (pin "1") (pinfunction "1_1") (pintype "passive"))
    )
    (net (code "51") (name "Net-(LED4-PadA)") (class "Default")
      (node (ref "LED4") (pin "A") (pinfunction "A_A") (pintype "passive"))
      (node (ref "R16") (pin "2") (pinfunction "2_2") (pintype "passive"))
      (node (ref "R23") (pin "2") (pinfunction "2_2") (pintype "passive"))
    )
    (net (code "52") (name "Net-(PWRLED-PadA)") (class "Default")
      (node (ref "PWRLED") (pin "A") (pinfunction "A_A") (pintype "passive"))
      (node (ref "R13") (pin "1") (pinfunction "1_1") (pintype "passive"))
    )
    (net (code "53") (name "Net-(Q1-D)") (class "Default")
      (node (ref "LED4") (pin "C") (pinfunction "C_C") (pintype "passive"))
      (node (ref "Q1") (pin "3") (pinfunction "D_3") (pintype "bidirectional"))
    )
    (net (code "54") (name "Net-(Q1-G)") (class "Default")
      (node (ref "Q1") (pin "1") (pinfunction "G_1") (pintype "tri_state"))
      (node (ref "R30") (pin "2") (pinfunction "2_2") (pintype "passive"))
      (node (ref "R33") (pin "1") (pinfunction "1_1") (pintype "passive"))
    )
    (net (code "55") (name "Net-(Q2-S)") (class "Default")
      (node (ref "Q2") (pin "4") (pinfunction "S_4") (pintype "passive"))
      (node (ref "S3") (pin "2") (pinfunction "P_2") (pintype "passive"))
    )
    (net (code "56") (name "Net-(R6-Pad2)") (class "Default")
      (node (ref "R6") (pin "2") (pinfunction "2_2") (pintype "passive"))
      (node (ref "U$2") (pin "D+") (pinfunction "D+_D+") (pintype "bidirectional"))
    )
    (net (code "57") (name "Net-(R7-Pad2)") (class "Default")
      (node (ref "R7") (pin "2") (pinfunction "2_2") (pintype "passive"))
      (node (ref "U$2") (pin "D-") (pinfunction "D-_D-") (pintype "bidirectional"))
    )
    (net (code "58") (name "Net-(R14-Pad2)") (class "Default")
      (node (ref "R14") (pin "2") (pinfunction "2_2") (pintype "passive"))
      (node (ref "RXLED") (pin "A") (pinfunction "A_A") (pintype "passive"))
    )
    (net (code "59") (name "Net-(R15-Pad2)") (class "Default")
      (node (ref "R15") (pin "2") (pinfunction "2_2") (pintype "passive"))
      (node (ref "TXLED") (pin "A") (pinfunction "A_A") (pintype "passive"))
    )
    (net (code "60") (name "Net-(R17-Pad1)") (class "Default")
      (node (ref "R17") (pin "1") (pinfunction "1_1") (pintype "passive"))
      (node (ref "R18") (pin "2") (pinfunction "2_2") (pintype "passive"))
      (node (ref "T1") (pin "B") (pinfunction "B_B") (pintype "passive"))
    )
    (net (code "61") (name "Net-(R24-A)") (class "Default")
      (node (ref "R12") (pin "1") (pinfunction "1_1") (pintype "passive"))
      (node (ref "R24") (pin "3") (pinfunction "A_3") (pintype "passive"))
    )
    (net (code "62") (name "Net-(R25-A)") (class "Default")
      (node (ref "R25") (pin "3") (pinfunction "A_3") (pintype "passive"))
      (node (ref "TSALXX") (pin "K") (pinfunction "C_K") (pintype "passive"))
    )
    (net (code "63") (name "Net-(R26-Pad2)") (class "Default")
      (node (ref "R26") (pin "2") (pinfunction "2_2") (pintype "passive"))
      (node (ref "U$11") (pin "P$2") (pinfunction "P$2_P$2") (pintype "bidirectional"))
    )
    (net (code "64") (name "Net-(R28-A)") (class "Default")
      (node (ref "R28") (pin "3") (pinfunction "A_3") (pintype "passive"))
      (node (ref "TSALXX1") (pin "K") (pinfunction "C_K") (pintype "passive"))
    )
    (net (code "65") (name "Net-(R29-Pad2)") (class "Default")
      (node (ref "R29") (pin "2") (pinfunction "2_2") (pintype "passive"))
      (node (ref "U$12") (pin "P$2") (pinfunction "P$2_P$2") (pintype "bidirectional"))
    )
    (net (code "66") (name "Net-(R31-A)") (class "Default")
      (node (ref "R31") (pin "3") (pinfunction "A_3") (pintype "passive"))
      (node (ref "U$11") (pin "P$1") (pinfunction "P$1_P$1") (pintype "bidirectional"))
    )
    (net (code "67") (name "Net-(R32-Pad2)") (class "Default")
      (node (ref "R32") (pin "2") (pinfunction "2_2") (pintype "passive"))
      (node (ref "TSALXX") (pin "A") (pinfunction "A_A") (pintype "passive"))
    )
    (net (code "68") (name "Net-(R34-A)") (class "Default")
      (node (ref "R34") (pin "3") (pinfunction "A_3") (pintype "passive"))
      (node (ref "U$12") (pin "P$1") (pinfunction "P$1_P$1") (pintype "bidirectional"))
    )
    (net (code "69") (name "Net-(R35-Pad2)") (class "Default")
      (node (ref "R35") (pin "2") (pinfunction "2_2") (pintype "passive"))
      (node (ref "TSALXX1") (pin "A") (pinfunction "A_A") (pintype "passive"))
    )
    (net (code "70") (name "Net-(R40-Pad2)") (class "Default")
      (node (ref "R40") (pin "2") (pinfunction "2_2") (pintype "passive"))
      (node (ref "RXLED1") (pin "A") (pinfunction "A_A") (pintype "passive"))
    )
    (net (code "71") (name "Net-(R41-Pad2)") (class "Default")
      (node (ref "R41") (pin "2") (pinfunction "2_2") (pintype "passive"))
      (node (ref "RXLED2") (pin "A") (pinfunction "A_A") (pintype "passive"))
    )
    (net (code "72") (name "Net-(R42-Pad2)") (class "Default")
      (node (ref "R42") (pin "2") (pinfunction "2_2") (pintype "passive"))
      (node (ref "RXLED3") (pin "A") (pinfunction "A_A") (pintype "passive"))
    )
    (net (code "73") (name "Net-(R43-Pad2)") (class "Default")
      (node (ref "R43") (pin "2") (pinfunction "2_2") (pintype "passive"))
      (node (ref "RXLED4") (pin "A") (pinfunction "A_A") (pintype "passive"))
    )
    (net (code "74") (name "Net-(S1-O)") (class "Default")
      (node (ref "R30") (pin "1") (pinfunction "1_1") (pintype "passive"))
      (node (ref "S1") (pin "1") (pinfunction "O_1") (pintype "passive"))
    )
    (net (code "75") (name "Net-(S2-O)") (class "Default")
      (node (ref "J2") (pin "PWR") (pinfunction "PWR_PWR") (pintype "bidirectional"))
      (node (ref "S2") (pin "1") (pinfunction "O_1") (pintype "passive"))
    )
    (net (code "76") (name "Net-(S2-S)") (class "Default")
      (node (ref "Q2") (pin "1") (pinfunction "D_1") (pintype "passive"))
      (node (ref "Q2") (pin "2") (pinfunction "D_2") (pintype "passive"))
      (node (ref "Q2") (pin "5") (pinfunction "D_5") (pintype "passive"))
      (node (ref "Q2") (pin "6") (pinfunction "D_6") (pintype "passive"))
      (node (ref "S2") (pin "3") (pinfunction "S_3") (pintype "passive"))
    )
    (net (code "77") (name "Net-(S4-O)") (class "Default")
      (node (ref "S4") (pin "1") (pinfunction "O_1") (pintype "passive"))
      (node (ref "S4") (pin "2") (pinfunction "P_2") (pintype "passive"))
      (node (ref "U$4") (pin "3") (pinfunction "D_3") (pintype "passive"))
    )
    (net (code "78") (name "Net-(SG1-Pad-)") (class "Default")
      (node (ref "SG1") (pin "-") (pinfunction "-_-") (pintype "passive"))
      (node (ref "T1") (pin "C") (pinfunction "C_C") (pintype "passive"))
    )
    (net (code "79") (name "Net-(U$1-AREF)") (class "Default")
      (node (ref "C1") (pin "1") (pinfunction "1_1") (pintype "passive"))
      (node (ref "U$1") (pin "42") (pinfunction "AREF_42") (pintype "bidirectional"))
    )
    (net (code "80") (name "Net-(U$1-PE2{slash}~{HWB})") (class "Default")
      (node (ref "R3") (pin "1") (pinfunction "1_1") (pintype "passive"))
      (node (ref "U$1") (pin "33") (pinfunction "PE2/~{HWB}_33") (pintype "bidirectional"))
    )
    (net (code "81") (name "Net-(U$1-UCAP)") (class "Default")
      (node (ref "C6") (pin "2") (pinfunction "2_2") (pintype "passive"))
      (node (ref "U$1") (pin "6") (pinfunction "UCAP_6") (pintype "bidirectional"))
    )
    (net (code "82") (name "Net-(U$1-XTAL2)") (class "Default")
      (node (ref "C3") (pin "2") (pinfunction "2_2") (pintype "passive"))
      (node (ref "CRYSTAL") (pin "1") (pinfunction "1_1") (pintype "passive"))
      (node (ref "R1") (pin "1") (pinfunction "1_1") (pintype "passive"))
      (node (ref "U$1") (pin "16") (pinfunction "XTAL2_16") (pintype "bidirectional"))
    )
    (net (code "83") (name "Net-(U$4-G)") (class "Default")
      (node (ref "R48") (pin "2") (pinfunction "2_2") (pintype "passive"))
      (node (ref "U$4") (pin "1") (pinfunction "G_1") (pintype "passive"))
    )
    (net (code "84") (name "RESET") (class "Default")
      (node (ref "D1") (pin "A") (pinfunction "A_A") (pintype "passive"))
      (node (ref "J1") (pin "5") (pinfunction "5_5") (pintype "passive"))
      (node (ref "R2") (pin "1") (pinfunction "1_1") (pintype "passive"))
      (node (ref "RESET_BUTTON") (pin "1") (pinfunction "1_1") (pintype "passive"))
      (node (ref "RESET_BUTTON") (pin "2") (pinfunction "2_2") (pintype "passive"))
      (node (ref "U$1") (pin "13") (pinfunction "~{RESET}_13") (pintype "bidirectional"))
    )
    (net (code "85") (name "RXLED") (class "Default")
      (node (ref "LCD(5110)") (pin "6") (pinfunction "6_6") (pintype "passive"))
      (node (ref "RXLED") (pin "C") (pinfunction "C_C") (pintype "passive"))
      (node (ref "U$1") (pin "8") (pinfunction "PB0(SS)_8") (pintype "bidirectional"))
    )
    (net (code "86") (name "SCK") (class "Default")
      (node (ref "J1") (pin "3") (pinfunction "3_3") (pintype "passive"))
      (node (ref "LCD(5110)") (pin "4") (pinfunction "4_4") (pintype "passive"))
      (node (ref "U$1") (pin "9") (pinfunction "PB1(SCK)_9") (pintype "bidirectional"))
    )
    (net (code "87") (name "SCL") (class "Default")
      (node (ref "I2C") (pin "3") (pinfunction "3_3") (pintype "passive"))
      (node (ref "R4") (pin "1") (pinfunction "1_1") (pintype "passive"))
      (node (ref "U$1") (pin "18") (pinfunction "PD0(SCL)_18") (pintype "bidirectional"))
    )
    (net (code "88") (name "SDA") (class "Default")
      (node (ref "I2C") (pin "4") (pinfunction "4_4") (pintype "passive"))
      (node (ref "R5") (pin "1") (pinfunction "1_1") (pintype "passive"))
      (node (ref "U$1") (pin "19") (pinfunction "PD1(SDA)_19") (pintype "bidirectional"))
    )
    (net (code "89") (name "TXLED") (class "Default")
      (node (ref "TXLED") (pin "C") (pinfunction "C_C") (pintype "passive"))
      (node (ref "U$1") (pin "22") (pinfunction "PD5_22") (pintype "bidirectional"))
    )
    (net (code "90") (name "VIN") (class "Default")
      (node (ref "C10") (pin "+") (pinfunction "+_+") (pintype "passive"))
      (node (ref "C21") (pin "1") (pinfunction "1_1") (pintype "passive"))
      (node (ref "IC2") (pin "5") (pinfunction "VIN_5") (pintype "power_in"))
      (node (ref "L2") (pin "1") (pinfunction "1_1") (pintype "passive"))
      (node (ref "S3") (pin "1") (pinfunction "O_1") (pintype "passive"))
    )
    (net (code "91") (name "VS1") (class "Default")
      (node (ref "C23") (pin "1") (pinfunction "1_1") (pintype "passive"))
      (node (ref "R19") (pin "1") (pinfunction "1_1") (pintype "passive"))
      (node (ref "U$9") (pin "VS") (pinfunction "VS_VS") (pintype "bidirectional"))
    )
    (net (code "92") (name "VS2") (class "Default")
      (node (ref "C24") (pin "1") (pinfunction "1_1") (pintype "passive"))
      (node (ref "R20") (pin "1") (pinfunction "1_1") (pintype "passive"))
      (node (ref "U$8") (pin "VS") (pinfunction "VS_VS") (pintype "bidirectional"))
    )
    (net (code "93") (name "VS3") (class "Default")
      (node (ref "C25") (pin "1") (pinfunction "1_1") (pintype "passive"))
      (node (ref "R21") (pin "1") (pinfunction "1_1") (pintype "passive"))
      (node (ref "U$6") (pin "2") (pinfunction "VS_2") (pintype "bidirectional"))
    )
    (net (code "94") (name "VS4") (class "Default")
      (node (ref "C26") (pin "1") (pinfunction "1_1") (pintype "passive"))
      (node (ref "R22") (pin "1") (pinfunction "1_1") (pintype "passive"))
      (node (ref "U$7") (pin "2") (pinfunction "VS_2") (pintype "bidirectional"))
    )
    (net (code "95") (name "VUSB") (class "Default")
      (node (ref "C8") (pin "1") (pinfunction "1_1") (pintype "passive"))
      (node (ref "C9") (pin "1") (pinfunction "1_1") (pintype "passive"))
      (node (ref "F1") (pin "1") (pinfunction "1_1") (pintype "passive"))
      (node (ref "T2") (pin "1") (pinfunction "D_1") (pintype "passive"))
      (node (ref "U$1") (pin "7") (pinfunction "VBUS_7") (pintype "bidirectional"))
    )
    (net (code "96") (name "V_BATT") (class "Default")
      (node (ref "C12") (pin "+") (pinfunction "+_+") (pintype "passive"))
      (node (ref "C13") (pin "1") (pinfunction "1_1") (pintype "passive"))
      (node (ref "C14") (pin "1") (pinfunction "1_1") (pintype "passive"))
      (node (ref "C16") (pin "1") (pinfunction "1_1") (pintype "passive"))
      (node (ref "C22") (pin "1") (pinfunction "1_1") (pintype "passive"))
      (node (ref "D2") (pin "1") (pinfunction "C_1") (pintype "passive"))
      (node (ref "R10") (pin "1") (pinfunction "1_1") (pintype "passive"))
      (node (ref "R49") (pin "2") (pinfunction "2_2") (pintype "passive"))
      (node (ref "S3") (pin "3") (pinfunction "S_3") (pintype "passive"))
      (node (ref "U$5") (pin "3") (pinfunction "VIN_3") (pintype "bidirectional"))
      (node (ref "U1") (pin "13") (pinfunction "VM2_13") (pintype "bidirectional"))
      (node (ref "U1") (pin "14") (pinfunction "VM3_14") (pintype "bidirectional"))
      (node (ref "U1") (pin "24") (pinfunction "VM1_24") (pintype "bidirectional"))
    )
    (net (code "97") (name "unconnected-(IC1-DIS-Pad7)") (class "Default")
      (node (ref "IC1") (pin "7") (pinfunction "DIS_7") (pintype "input"))
    )
    (net (code "98") (name "unconnected-(R24-E-Pad1)") (class "Default")
      (node (ref "R24") (pin "1") (pinfunction "E_1") (pintype "passive"))
    )
    (net (code "99") (name "unconnected-(R25-E-Pad1)") (class "Default")
      (node (ref "R25") (pin "1") (pinfunction "E_1") (pintype "passive"))
    )
    (net (code "100") (name "unconnected-(R28-E-Pad1)") (class "Default")
      (node (ref "R28") (pin "1") (pinfunction "E_1") (pintype "passive"))
    )
    (net (code "101") (name "unconnected-(R31-E-Pad1)") (class "Default")
      (node (ref "R31") (pin "1") (pinfunction "E_1") (pintype "passive"))
    )
    (net (code "102") (name "unconnected-(R34-E-Pad1)") (class "Default")
      (node (ref "R34") (pin "1") (pinfunction "E_1") (pintype "passive"))
    )
  )
)
